# 14-Counter74LS192.net
KiCad netlist of a schematic drawn in Altium Designer
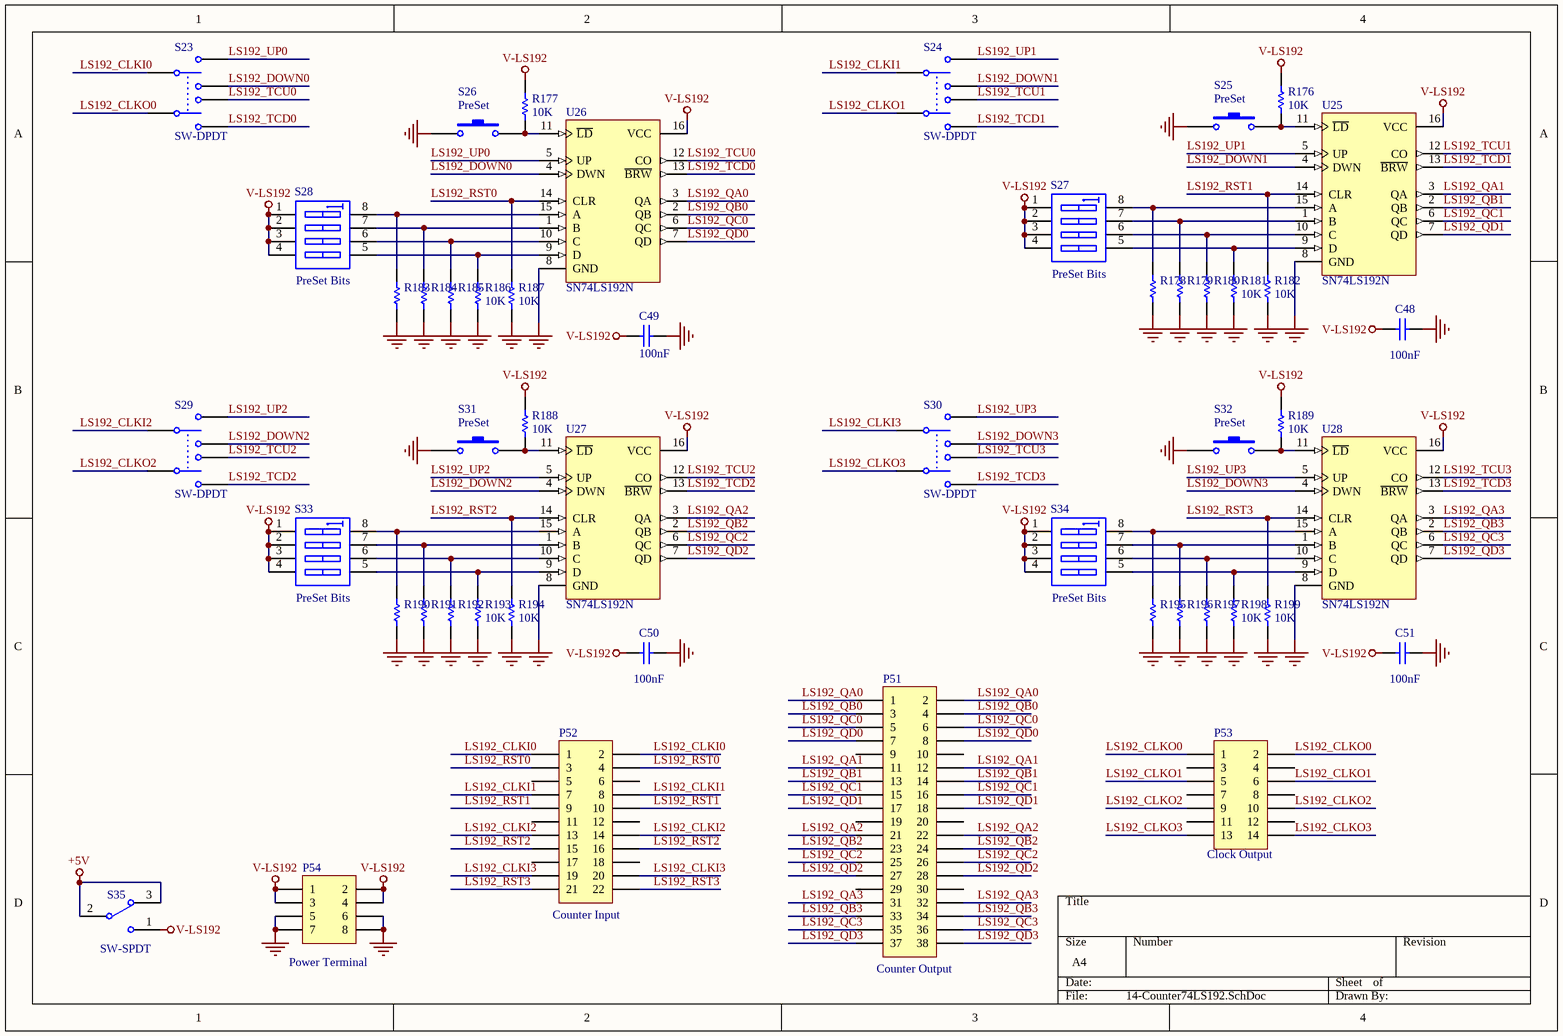
[diagram p0: 14-Counter74LS192.SchDoc]

(export (version "E")
  (design (tool "Eeschema 10.0.6"))
  (components
    (comp (ref "C48")
      (value "100nF")
      (footprint "c-0805")
      (description "Capacitor")
      (fields (field (name "Comment") "104") (field (name "PUBLISHER") "Altium Limited"))
      (libsource (lib "Miscellaneous Devices") (part "Cap"))
    )
    (comp (ref "C49")
      (value "100nF")
      (footprint "c-0805")
      (description "Capacitor")
      (fields (field (name "Comment") "104") (field (name "PUBLISHER") "Altium Limited"))
      (libsource (lib "Miscellaneous Devices") (part "Cap"))
    )
    (comp (ref "C50")
      (value "100nF")
      (footprint "c-0805")
      (description "Capacitor")
      (fields (field (name "Comment") "104") (field (name "PUBLISHER") "Altium Limited"))
      (libsource (lib "Miscellaneous Devices") (part "Cap"))
    )
    (comp (ref "C51")
      (value "100nF")
      (footprint "c-0805")
      (description "Capacitor")
      (fields (field (name "Comment") "104") (field (name "PUBLISHER") "Altium Limited"))
      (libsource (lib "Miscellaneous Devices") (part "Cap"))
    )
    (comp (ref "P51")
      (value "Counter Output")
      (footprint "HDR2X19")
      (description "Header, 19-Pin, Dual row")
      (fields (field (name "Comment") "Header 19X2"))
      (libsource (lib "Miscellaneous Connectors") (part "Header 19X2"))
    )
    (comp (ref "P52")
      (value "Counter Input")
      (footprint "HDR2X11")
      (description "Header, 11-Pin, Dual row")
      (fields (field (name "Comment") "Header 11X2"))
      (libsource (lib "Miscellaneous Connectors") (part "Header 11X2"))
    )
    (comp (ref "P53")
      (value "Clock Output")
      (footprint "HDR2X7")
      (description "Header, 7-Pin, Dual row")
      (fields (field (name "Comment") "Header 7X2"))
      (libsource (lib "Miscellaneous Connectors") (part "Header 7X2"))
    )
    (comp (ref "P54")
      (value "Header 4X2")
      (footprint "HDR2X4")
      (description "Header, 4-Pin, Dual row")
      (fields (field (name "PUBLISHER") "Power Terminal"))
      (libsource (lib "Miscellaneous Connectors") (part "Header 4X2"))
    )
    (comp (ref "R176")
      (value "10K")
      (footprint "r-0805")
      (description "Resistor")
      (fields (field (name "PUBLISHER") "Altium Limited"))
      (libsource (lib "Miscellaneous Devices") (part "Res1"))
    )
    (comp (ref "R177")
      (value "10K")
      (footprint "r-0805")
      (description "Resistor")
      (fields (field (name "PUBLISHER") "Altium Limited"))
      (libsource (lib "Miscellaneous Devices") (part "Res1"))
    )
    (comp (ref "R178")
      (value "103")
      (footprint "r-0805")
      (description "Resistor")
      (fields (field (name "PUBLISHER") "Altium Limited"))
      (libsource (lib "Miscellaneous Devices") (part "Res1"))
    )
    (comp (ref "R179")
      (value "103")
      (footprint "r-0805")
      (description "Resistor")
      (fields (field (name "PUBLISHER") "Altium Limited"))
      (libsource (lib "Miscellaneous Devices") (part "Res1"))
    )
    (comp (ref "R180")
      (value "103")
      (footprint "r-0805")
      (description "Resistor")
      (fields (field (name "PUBLISHER") "Altium Limited"))
      (libsource (lib "Miscellaneous Devices") (part "Res1"))
    )
    (comp (ref "R181")
      (value "10K")
      (footprint "r-0805")
      (description "Resistor")
      (fields (field (name "PUBLISHER") "Altium Limited"))
      (libsource (lib "Miscellaneous Devices") (part "Res1"))
    )
    (comp (ref "R182")
      (value "10K")
      (footprint "r-0805")
      (description "Resistor")
      (fields (field (name "PUBLISHER") "Altium Limited"))
      (libsource (lib "Miscellaneous Devices") (part "Res1"))
    )
    (comp (ref "R183")
      (value "103")
      (footprint "r-0805")
      (description "Resistor")
      (fields (field (name "PUBLISHER") "Altium Limited"))
      (libsource (lib "Miscellaneous Devices") (part "Res1"))
    )
    (comp (ref "R184")
      (value "103")
      (footprint "r-0805")
      (description "Resistor")
      (fields (field (name "PUBLISHER") "Altium Limited"))
      (libsource (lib "Miscellaneous Devices") (part "Res1"))
    )
    (comp (ref "R185")
      (value "103")
      (footprint "r-0805")
      (description "Resistor")
      (fields (field (name "PUBLISHER") "Altium Limited"))
      (libsource (lib "Miscellaneous Devices") (part "Res1"))
    )
    (comp (ref "R186")
      (value "10K")
      (footprint "r-0805")
      (description "Resistor")
      (fields (field (name "PUBLISHER") "Altium Limited"))
      (libsource (lib "Miscellaneous Devices") (part "Res1"))
    )
    (comp (ref "R187")
      (value "10K")
      (footprint "r-0805")
      (description "Resistor")
      (fields (field (name "PUBLISHER") "Altium Limited"))
      (libsource (lib "Miscellaneous Devices") (part "Res1"))
    )
    (comp (ref "R188")
      (value "10K")
      (footprint "r-0805")
      (description "Resistor")
      (fields (field (name "PUBLISHER") "Altium Limited"))
      (libsource (lib "Miscellaneous Devices") (part "Res1"))
    )
    (comp (ref "R189")
      (value "10K")
      (footprint "r-0805")
      (description "Resistor")
      (fields (field (name "PUBLISHER") "Altium Limited"))
      (libsource (lib "Miscellaneous Devices") (part "Res1"))
    )
    (comp (ref "R190")
      (value "103")
      (footprint "r-0805")
      (description "Resistor")
      (fields (field (name "PUBLISHER") "Altium Limited"))
      (libsource (lib "Miscellaneous Devices") (part "Res1"))
    )
    (comp (ref "R191")
      (value "103")
      (footprint "r-0805")
      (description "Resistor")
      (fields (field (name "PUBLISHER") "Altium Limited"))
      (libsource (lib "Miscellaneous Devices") (part "Res1"))
    )
    (comp (ref "R192")
      (value "103")
      (footprint "r-0805")
      (description "Resistor")
      (fields (field (name "PUBLISHER") "Altium Limited"))
      (libsource (lib "Miscellaneous Devices") (part "Res1"))
    )
    (comp (ref "R193")
      (value "10K")
      (footprint "r-0805")
      (description "Resistor")
      (fields (field (name "PUBLISHER") "Altium Limited"))
      (libsource (lib "Miscellaneous Devices") (part "Res1"))
    )
    (comp (ref "R194")
      (value "10K")
      (footprint "r-0805")
      (description "Resistor")
      (fields (field (name "PUBLISHER") "Altium Limited"))
      (libsource (lib "Miscellaneous Devices") (part "Res1"))
    )
    (comp (ref "R195")
      (value "103")
      (footprint "r-0805")
      (description "Resistor")
      (fields (field (name "PUBLISHER") "Altium Limited"))
      (libsource (lib "Miscellaneous Devices") (part "Res1"))
    )
    (comp (ref "R196")
      (value "103")
      (footprint "r-0805")
      (description "Resistor")
      (fields (field (name "PUBLISHER") "Altium Limited"))
      (libsource (lib "Miscellaneous Devices") (part "Res1"))
    )
    (comp (ref "R197")
      (value "103")
      (footprint "r-0805")
      (description "Resistor")
      (fields (field (name "PUBLISHER") "Altium Limited"))
      (libsource (lib "Miscellaneous Devices") (part "Res1"))
    )
    (comp (ref "R198")
      (value "10K")
      (footprint "r-0805")
      (description "Resistor")
      (fields (field (name "PUBLISHER") "Altium Limited"))
      (libsource (lib "Miscellaneous Devices") (part "Res1"))
    )
    (comp (ref "R199")
      (value "10K")
      (footprint "r-0805")
      (description "Resistor")
      (fields (field (name "PUBLISHER") "Altium Limited"))
      (libsource (lib "Miscellaneous Devices") (part "Res1"))
    )
    (comp (ref "S23")
      (value "SW-DPDT")
      (footprint "DPDT-6")
      (description "Double-Pole, Double-Throw Switch")
      (fields (field (name "PUBLISHER") "Altium Limited"))
      (libsource (lib "Miscellaneous Devices") (part "SW-DPDT"))
    )
    (comp (ref "S24")
      (value "SW-DPDT")
      (footprint "DPDT-6")
      (description "Double-Pole, Double-Throw Switch")
      (fields (field (name "PUBLISHER") "Altium Limited"))
      (libsource (lib "Miscellaneous Devices") (part "SW-DPDT"))
    )
    (comp (ref "S25")
      (value "PreSet")
      (footprint "SW2")
      (description "Switch")
      (fields (field (name "Comment") "SW-PB"))
      (libsource (lib "Miscellaneous Devices") (part "SW-PB"))
    )
    (comp (ref "S26")
      (value "PreSet")
      (footprint "SW2")
      (description "Switch")
      (fields (field (name "Comment") "SW-PB"))
      (libsource (lib "Miscellaneous Devices") (part "SW-PB"))
    )
    (comp (ref "S27")
      (value "PreSet Bits")
      (footprint "SW-DIP4")
      (description "DIP Switch, 4 Position, SPST")
      (fields (field (name "Comment") "SW DIP-4"))
      (libsource (lib "Miscellaneous Devices") (part "SW DIP-4"))
    )
    (comp (ref "S28")
      (value "PreSet Bits")
      (footprint "SW-DIP4")
      (description "DIP Switch, 4 Position, SPST")
      (fields (field (name "Comment") "SW DIP-4"))
      (libsource (lib "Miscellaneous Devices") (part "SW DIP-4"))
    )
    (comp (ref "S29")
      (value "SW-DPDT")
      (footprint "DPDT-6")
      (description "Double-Pole, Double-Throw Switch")
      (fields (field (name "PUBLISHER") "Altium Limited"))
      (libsource (lib "Miscellaneous Devices") (part "SW-DPDT"))
    )
    (comp (ref "S30")
      (value "SW-DPDT")
      (footprint "DPDT-6")
      (description "Double-Pole, Double-Throw Switch")
      (fields (field (name "PUBLISHER") "Altium Limited"))
      (libsource (lib "Miscellaneous Devices") (part "SW-DPDT"))
    )
    (comp (ref "S31")
      (value "PreSet")
      (footprint "SW2")
      (description "Switch")
      (fields (field (name "Comment") "SW-PB"))
      (libsource (lib "Miscellaneous Devices") (part "SW-PB"))
    )
    (comp (ref "S32")
      (value "PreSet")
      (footprint "SW2")
      (description "Switch")
      (fields (field (name "Comment") "SW-PB"))
      (libsource (lib "Miscellaneous Devices") (part "SW-PB"))
    )
    (comp (ref "S33")
      (value "PreSet Bits")
      (footprint "SW-DIP4")
      (description "DIP Switch, 4 Position, SPST")
      (fields (field (name "Comment") "SW DIP-4"))
      (libsource (lib "Miscellaneous Devices") (part "SW DIP-4"))
    )
    (comp (ref "S34")
      (value "PreSet Bits")
      (footprint "SW-DIP4")
      (description "DIP Switch, 4 Position, SPST")
      (fields (field (name "Comment") "SW DIP-4"))
      (libsource (lib "Miscellaneous Devices") (part "SW DIP-4"))
    )
    (comp (ref "S35")
      (value "SW-SPDT")
      (footprint "SW-DIP1SMD")
      (description "SPDT Subminiature Toggle Switch, Right Angle Mounting, Vertical Actuation")
      (fields (field (name "PUBLISHER") "Altium Limited"))
      (libsource (lib "Miscellaneous Devices") (part "SW-SPDT"))
    )
    (comp (ref "U25")
      (value "SN74LS192N")
      (footprint "DIP16")
      (description "Synchronous 4-Bit Up/Down Counter (Dual Clock with Clear)")
      (fields (field (name "PUBLISHER") "Altium Limited"))
      (libsource (lib "TI Logic Counter") (part "SN74LS192N"))
    )
    (comp (ref "U26")
      (value "SN74LS192N")
      (footprint "DIP16")
      (description "Synchronous 4-Bit Up/Down Counter (Dual Clock with Clear)")
      (fields (field (name "PUBLISHER") "Altium Limited"))
      (libsource (lib "TI Logic Counter") (part "SN74LS192N"))
    )
    (comp (ref "U27")
      (value "SN74LS192N")
      (footprint "DIP16")
      (description "Synchronous 4-Bit Up/Down Counter (Dual Clock with Clear)")
      (fields (field (name "PUBLISHER") "Altium Limited"))
      (libsource (lib "TI Logic Counter") (part "SN74LS192N"))
    )
    (comp (ref "U28")
      (value "SN74LS192N")
      (footprint "DIP16")
      (description "Synchronous 4-Bit Up/Down Counter (Dual Clock with Clear)")
      (fields (field (name "PUBLISHER") "Altium Limited"))
      (libsource (lib "TI Logic Counter") (part "SN74LS192N"))
    )
  )
  (nets
    (net (code "1") (name "+5V") (class "Default")
      (node (ref "S35") (pin "2") (pinfunction "2_2") (pintype "passive"))
      (node (ref "S35") (pin "3") (pinfunction "3_3") (pintype "passive"))
    )
    (net (code "2") (name "/LS192_CLKI0") (class "Default")
      (node (ref "P52") (pin "1") (pinfunction "1_1") (pintype "passive"))
      (node (ref "P52") (pin "2") (pinfunction "2_2") (pintype "passive"))
      (node (ref "S23") (pin "1") (pinfunction "1_1") (pintype "passive"))
    )
    (net (code "3") (name "/LS192_CLKI1") (class "Default")
      (node (ref "P52") (pin "7") (pinfunction "7_7") (pintype "passive"))
      (node (ref "P52") (pin "8") (pinfunction "8_8") (pintype "passive"))
      (node (ref "S24") (pin "1") (pinfunction "1_1") (pintype "passive"))
    )
    (net (code "4") (name "/LS192_CLKI2") (class "Default")
      (node (ref "P52") (pin "13") (pinfunction "13_13") (pintype "passive"))
      (node (ref "P52") (pin "14") (pinfunction "14_14") (pintype "passive"))
      (node (ref "S29") (pin "1") (pinfunction "1_1") (pintype "passive"))
    )
    (net (code "5") (name "/LS192_CLKI3") (class "Default")
      (node (ref "P52") (pin "19") (pinfunction "19_19") (pintype "passive"))
      (node (ref "P52") (pin "20") (pinfunction "20_20") (pintype "passive"))
      (node (ref "S30") (pin "1") (pinfunction "1_1") (pintype "passive"))
    )
    (net (code "6") (name "/LS192_CLKO0") (class "Default")
      (node (ref "P53") (pin "1") (pinfunction "1_1") (pintype "passive"))
      (node (ref "P53") (pin "2") (pinfunction "2_2") (pintype "passive"))
      (node (ref "S23") (pin "4") (pinfunction "4_4") (pintype "passive"))
    )
    (net (code "7") (name "/LS192_CLKO1") (class "Default")
      (node (ref "P53") (pin "5") (pinfunction "5_5") (pintype "passive"))
      (node (ref "P53") (pin "6") (pinfunction "6_6") (pintype "passive"))
      (node (ref "S24") (pin "4") (pinfunction "4_4") (pintype "passive"))
    )
    (net (code "8") (name "/LS192_CLKO2") (class "Default")
      (node (ref "P53") (pin "10") (pinfunction "10_10") (pintype "passive"))
      (node (ref "P53") (pin "9") (pinfunction "9_9") (pintype "passive"))
      (node (ref "S29") (pin "4") (pinfunction "4_4") (pintype "passive"))
    )
    (net (code "9") (name "/LS192_CLKO3") (class "Default")
      (node (ref "P53") (pin "13") (pinfunction "13_13") (pintype "passive"))
      (node (ref "P53") (pin "14") (pinfunction "14_14") (pintype "passive"))
      (node (ref "S30") (pin "4") (pinfunction "4_4") (pintype "passive"))
    )
    (net (code "10") (name "/LS192_DOWN0") (class "Default")
      (node (ref "S23") (pin "3") (pinfunction "3_3") (pintype "passive"))
      (node (ref "U26") (pin "4") (pinfunction "DWN_4") (pintype "input"))
    )
    (net (code "11") (name "/LS192_DOWN1") (class "Default")
      (node (ref "S24") (pin "3") (pinfunction "3_3") (pintype "passive"))
      (node (ref "U25") (pin "4") (pinfunction "DWN_4") (pintype "input"))
    )
    (net (code "12") (name "/LS192_DOWN2") (class "Default")
      (node (ref "S29") (pin "3") (pinfunction "3_3") (pintype "passive"))
      (node (ref "U27") (pin "4") (pinfunction "DWN_4") (pintype "input"))
    )
    (net (code "13") (name "/LS192_DOWN3") (class "Default")
      (node (ref "S30") (pin "3") (pinfunction "3_3") (pintype "passive"))
      (node (ref "U28") (pin "4") (pinfunction "DWN_4") (pintype "input"))
    )
    (net (code "14") (name "/LS192_QA0") (class "Default")
      (node (ref "P51") (pin "1") (pinfunction "1_1") (pintype "passive"))
      (node (ref "P51") (pin "2") (pinfunction "2_2") (pintype "passive"))
      (node (ref "U26") (pin "3") (pinfunction "QA_3") (pintype "output"))
    )
    (net (code "15") (name "/LS192_QA1") (class "Default")
      (node (ref "P51") (pin "11") (pinfunction "11_11") (pintype "passive"))
      (node (ref "P51") (pin "12") (pinfunction "12_12") (pintype "passive"))
      (node (ref "U25") (pin "3") (pinfunction "QA_3") (pintype "output"))
    )
    (net (code "16") (name "/LS192_QA2") (class "Default")
      (node (ref "P51") (pin "21") (pinfunction "21_21") (pintype "passive"))
      (node (ref "P51") (pin "22") (pinfunction "22_22") (pintype "passive"))
      (node (ref "U27") (pin "3") (pinfunction "QA_3") (pintype "output"))
    )
    (net (code "17") (name "/LS192_QA3") (class "Default")
      (node (ref "P51") (pin "31") (pinfunction "31_31") (pintype "passive"))
      (node (ref "P51") (pin "32") (pinfunction "32_32") (pintype "passive"))
      (node (ref "U28") (pin "3") (pinfunction "QA_3") (pintype "output"))
    )
    (net (code "18") (name "/LS192_QB0") (class "Default")
      (node (ref "P51") (pin "3") (pinfunction "3_3") (pintype "passive"))
      (node (ref "P51") (pin "4") (pinfunction "4_4") (pintype "passive"))
      (node (ref "U26") (pin "2") (pinfunction "QB_2") (pintype "output"))
    )
    (net (code "19") (name "/LS192_QB1") (class "Default")
      (node (ref "P51") (pin "13") (pinfunction "13_13") (pintype "passive"))
      (node (ref "P51") (pin "14") (pinfunction "14_14") (pintype "passive"))
      (node (ref "U25") (pin "2") (pinfunction "QB_2") (pintype "output"))
    )
    (net (code "20") (name "/LS192_QB2") (class "Default")
      (node (ref "P51") (pin "23") (pinfunction "23_23") (pintype "passive"))
      (node (ref "P51") (pin "24") (pinfunction "24_24") (pintype "passive"))
      (node (ref "U27") (pin "2") (pinfunction "QB_2") (pintype "output"))
    )
    (net (code "21") (name "/LS192_QB3") (class "Default")
      (node (ref "P51") (pin "33") (pinfunction "33_33") (pintype "passive"))
      (node (ref "P51") (pin "34") (pinfunction "34_34") (pintype "passive"))
      (node (ref "U28") (pin "2") (pinfunction "QB_2") (pintype "output"))
    )
    (net (code "22") (name "/LS192_QC0") (class "Default")
      (node (ref "P51") (pin "5") (pinfunction "5_5") (pintype "passive"))
      (node (ref "P51") (pin "6") (pinfunction "6_6") (pintype "passive"))
      (node (ref "U26") (pin "6") (pinfunction "QC_6") (pintype "output"))
    )
    (net (code "23") (name "/LS192_QC1") (class "Default")
      (node (ref "P51") (pin "15") (pinfunction "15_15") (pintype "passive"))
      (node (ref "P51") (pin "16") (pinfunction "16_16") (pintype "passive"))
      (node (ref "U25") (pin "6") (pinfunction "QC_6") (pintype "output"))
    )
    (net (code "24") (name "/LS192_QC2") (class "Default")
      (node (ref "P51") (pin "25") (pinfunction "25_25") (pintype "passive"))
      (node (ref "P51") (pin "26") (pinfunction "26_26") (pintype "passive"))
      (node (ref "U27") (pin "6") (pinfunction "QC_6") (pintype "output"))
    )
    (net (code "25") (name "/LS192_QC3") (class "Default")
      (node (ref "P51") (pin "35") (pinfunction "35_35") (pintype "passive"))
      (node (ref "P51") (pin "36") (pinfunction "36_36") (pintype "passive"))
      (node (ref "U28") (pin "6") (pinfunction "QC_6") (pintype "output"))
    )
    (net (code "26") (name "/LS192_QD0") (class "Default")
      (node (ref "P51") (pin "7") (pinfunction "7_7") (pintype "passive"))
      (node (ref "P51") (pin "8") (pinfunction "8_8") (pintype "passive"))
      (node (ref "U26") (pin "7") (pinfunction "QD_7") (pintype "output"))
    )
    (net (code "27") (name "/LS192_QD1") (class "Default")
      (node (ref "P51") (pin "17") (pinfunction "17_17") (pintype "passive"))
      (node (ref "P51") (pin "18") (pinfunction "18_18") (pintype "passive"))
      (node (ref "U25") (pin "7") (pinfunction "QD_7") (pintype "output"))
    )
    (net (code "28") (name "/LS192_QD2") (class "Default")
      (node (ref "P51") (pin "27") (pinfunction "27_27") (pintype "passive"))
      (node (ref "P51") (pin "28") (pinfunction "28_28") (pintype "passive"))
      (node (ref "U27") (pin "7") (pinfunction "QD_7") (pintype "output"))
    )
    (net (code "29") (name "/LS192_QD3") (class "Default")
      (node (ref "P51") (pin "37") (pinfunction "37_37") (pintype "passive"))
      (node (ref "P51") (pin "38") (pinfunction "38_38") (pintype "passive"))
      (node (ref "U28") (pin "7") (pinfunction "QD_7") (pintype "output"))
    )
    (net (code "30") (name "/LS192_RST0") (class "Default")
      (node (ref "P52") (pin "3") (pinfunction "3_3") (pintype "passive"))
      (node (ref "P52") (pin "4") (pinfunction "4_4") (pintype "passive"))
      (node (ref "R187") (pin "2") (pinfunction "2_2") (pintype "passive"))
      (node (ref "U26") (pin "14") (pinfunction "CLR_14") (pintype "input"))
    )
    (net (code "31") (name "/LS192_RST1") (class "Default")
      (node (ref "P52") (pin "10") (pinfunction "10_10") (pintype "passive"))
      (node (ref "P52") (pin "9") (pinfunction "9_9") (pintype "passive"))
      (node (ref "R182") (pin "2") (pinfunction "2_2") (pintype "passive"))
      (node (ref "U25") (pin "14") (pinfunction "CLR_14") (pintype "input"))
    )
    (net (code "32") (name "/LS192_RST2") (class "Default")
      (node (ref "P52") (pin "15") (pinfunction "15_15") (pintype "passive"))
      (node (ref "P52") (pin "16") (pinfunction "16_16") (pintype "passive"))
      (node (ref "R194") (pin "2") (pinfunction "2_2") (pintype "passive"))
      (node (ref "U27") (pin "14") (pinfunction "CLR_14") (pintype "input"))
    )
    (net (code "33") (name "/LS192_RST3") (class "Default")
      (node (ref "P52") (pin "21") (pinfunction "21_21") (pintype "passive"))
      (node (ref "P52") (pin "22") (pinfunction "22_22") (pintype "passive"))
      (node (ref "R199") (pin "2") (pinfunction "2_2") (pintype "passive"))
      (node (ref "U28") (pin "14") (pinfunction "CLR_14") (pintype "input"))
    )
    (net (code "34") (name "/LS192_TCD0") (class "Default")
      (node (ref "S23") (pin "6") (pinfunction "6_6") (pintype "passive"))
      (node (ref "U26") (pin "13") (pinfunction "~{BRW}_13") (pintype "output"))
    )
    (net (code "35") (name "/LS192_TCD1") (class "Default")
      (node (ref "S24") (pin "6") (pinfunction "6_6") (pintype "passive"))
      (node (ref "U25") (pin "13") (pinfunction "~{BRW}_13") (pintype "output"))
    )
    (net (code "36") (name "/LS192_TCD2") (class "Default")
      (node (ref "S29") (pin "6") (pinfunction "6_6") (pintype "passive"))
      (node (ref "U27") (pin "13") (pinfunction "~{BRW}_13") (pintype "output"))
    )
    (net (code "37") (name "/LS192_TCD3") (class "Default")
      (node (ref "S30") (pin "6") (pinfunction "6_6") (pintype "passive"))
      (node (ref "U28") (pin "13") (pinfunction "~{BRW}_13") (pintype "output"))
    )
    (net (code "38") (name "/LS192_TCU0") (class "Default")
      (node (ref "S23") (pin "5") (pinfunction "5_5") (pintype "passive"))
      (node (ref "U26") (pin "12") (pinfunction "CO_12") (pintype "output"))
    )
    (net (code "39") (name "/LS192_TCU1") (class "Default")
      (node (ref "S24") (pin "5") (pinfunction "5_5") (pintype "passive"))
      (node (ref "U25") (pin "12") (pinfunction "CO_12") (pintype "output"))
    )
    (net (code "40") (name "/LS192_TCU2") (class "Default")
      (node (ref "S29") (pin "5") (pinfunction "5_5") (pintype "passive"))
      (node (ref "U27") (pin "12") (pinfunction "CO_12") (pintype "output"))
    )
    (net (code "41") (name "/LS192_TCU3") (class "Default")
      (node (ref "S30") (pin "5") (pinfunction "5_5") (pintype "passive"))
      (node (ref "U28") (pin "12") (pinfunction "CO_12") (pintype "output"))
    )
    (net (code "42") (name "/LS192_UP0") (class "Default")
      (node (ref "S23") (pin "2") (pinfunction "2_2") (pintype "passive"))
      (node (ref "U26") (pin "5") (pinfunction "UP_5") (pintype "input"))
    )
    (net (code "43") (name "/LS192_UP1") (class "Default")
      (node (ref "S24") (pin "2") (pinfunction "2_2") (pintype "passive"))
      (node (ref "U25") (pin "5") (pinfunction "UP_5") (pintype "input"))
    )
    (net (code "44") (name "/LS192_UP2") (class "Default")
      (node (ref "S29") (pin "2") (pinfunction "2_2") (pintype "passive"))
      (node (ref "U27") (pin "5") (pinfunction "UP_5") (pintype "input"))
    )
    (net (code "45") (name "/LS192_UP3") (class "Default")
      (node (ref "S30") (pin "2") (pinfunction "2_2") (pintype "passive"))
      (node (ref "U28") (pin "5") (pinfunction "UP_5") (pintype "input"))
    )
    (net (code "46") (name "GND") (class "Default")
      (node (ref "C48") (pin "2") (pinfunction "2_2") (pintype "passive"))
      (node (ref "C49") (pin "2") (pinfunction "2_2") (pintype "passive"))
      (node (ref "C50") (pin "2") (pinfunction "2_2") (pintype "passive"))
      (node (ref "C51") (pin "2") (pinfunction "2_2") (pintype "passive"))
      (node (ref "P54") (pin "5") (pinfunction "5_5") (pintype "passive"))
      (node (ref "P54") (pin "6") (pinfunction "6_6") (pintype "passive"))
      (node (ref "P54") (pin "7") (pinfunction "7_7") (pintype "passive"))
      (node (ref "P54") (pin "8") (pinfunction "8_8") (pintype "passive"))
      (node (ref "R178") (pin "1") (pinfunction "1_1") (pintype "passive"))
      (node (ref "R179") (pin "1") (pinfunction "1_1") (pintype "passive"))
      (node (ref "R180") (pin "1") (pinfunction "1_1") (pintype "passive"))
      (node (ref "R181") (pin "1") (pinfunction "1_1") (pintype "passive"))
      (node (ref "R182") (pin "1") (pinfunction "1_1") (pintype "passive"))
      (node (ref "R183") (pin "1") (pinfunction "1_1") (pintype "passive"))
      (node (ref "R184") (pin "1") (pinfunction "1_1") (pintype "passive"))
      (node (ref "R185") (pin "1") (pinfunction "1_1") (pintype "passive"))
      (node (ref "R186") (pin "1") (pinfunction "1_1") (pintype "passive"))
      (node (ref "R187") (pin "1") (pinfunction "1_1") (pintype "passive"))
      (node (ref "R190") (pin "1") (pinfunction "1_1") (pintype "passive"))
      (node (ref "R191") (pin "1") (pinfunction "1_1") (pintype "passive"))
      (node (ref "R192") (pin "1") (pinfunction "1_1") (pintype "passive"))
      (node (ref "R193") (pin "1") (pinfunction "1_1") (pintype "passive"))
      (node (ref "R194") (pin "1") (pinfunction "1_1") (pintype "passive"))
      (node (ref "R195") (pin "1") (pinfunction "1_1") (pintype "passive"))
      (node (ref "R196") (pin "1") (pinfunction "1_1") (pintype "passive"))
      (node (ref "R197") (pin "1") (pinfunction "1_1") (pintype "passive"))
      (node (ref "R198") (pin "1") (pinfunction "1_1") (pintype "passive"))
      (node (ref "R199") (pin "1") (pinfunction "1_1") (pintype "passive"))
      (node (ref "S25") (pin "1") (pinfunction "1_1") (pintype "passive"))
      (node (ref "S26") (pin "1") (pinfunction "1_1") (pintype "passive"))
      (node (ref "S31") (pin "1") (pinfunction "1_1") (pintype "passive"))
      (node (ref "S32") (pin "1") (pinfunction "1_1") (pintype "passive"))
      (node (ref "U25") (pin "8") (pinfunction "GND_8") (pintype "power_in"))
      (node (ref "U26") (pin "8") (pinfunction "GND_8") (pintype "power_in"))
      (node (ref "U27") (pin "8") (pinfunction "GND_8") (pintype "power_in"))
      (node (ref "U28") (pin "8") (pinfunction "GND_8") (pintype "power_in"))
    )
    (net (code "47") (name "Net-(S27-B1)") (class "Default")
      (node (ref "R178") (pin "2") (pinfunction "2_2") (pintype "passive"))
      (node (ref "S27") (pin "8") (pinfunction "B1_8") (pintype "passive"))
      (node (ref "U25") (pin "15") (pinfunction "A_15") (pintype "input"))
    )
    (net (code "48") (name "Net-(S27-B2)") (class "Default")
      (node (ref "R179") (pin "2") (pinfunction "2_2") (pintype "passive"))
      (node (ref "S27") (pin "7") (pinfunction "B2_7") (pintype "passive"))
      (node (ref "U25") (pin "1") (pinfunction "B_1") (pintype "input"))
    )
    (net (code "49") (name "Net-(S27-B3)") (class "Default")
      (node (ref "R180") (pin "2") (pinfunction "2_2") (pintype "passive"))
      (node (ref "S27") (pin "6") (pinfunction "B3_6") (pintype "passive"))
      (node (ref "U25") (pin "10") (pinfunction "C_10") (pintype "input"))
    )
    (net (code "50") (name "Net-(S27-B4)") (class "Default")
      (node (ref "R181") (pin "2") (pinfunction "2_2") (pintype "passive"))
      (node (ref "S27") (pin "5") (pinfunction "B4_5") (pintype "passive"))
      (node (ref "U25") (pin "9") (pinfunction "D_9") (pintype "input"))
    )
    (net (code "51") (name "Net-(S28-B1)") (class "Default")
      (node (ref "R183") (pin "2") (pinfunction "2_2") (pintype "passive"))
      (node (ref "S28") (pin "8") (pinfunction "B1_8") (pintype "passive"))
      (node (ref "U26") (pin "15") (pinfunction "A_15") (pintype "input"))
    )
    (net (code "52") (name "Net-(S28-B2)") (class "Default")
      (node (ref "R184") (pin "2") (pinfunction "2_2") (pintype "passive"))
      (node (ref "S28") (pin "7") (pinfunction "B2_7") (pintype "passive"))
      (node (ref "U26") (pin "1") (pinfunction "B_1") (pintype "input"))
    )
    (net (code "53") (name "Net-(S28-B3)") (class "Default")
      (node (ref "R185") (pin "2") (pinfunction "2_2") (pintype "passive"))
      (node (ref "S28") (pin "6") (pinfunction "B3_6") (pintype "passive"))
      (node (ref "U26") (pin "10") (pinfunction "C_10") (pintype "input"))
    )
    (net (code "54") (name "Net-(S28-B4)") (class "Default")
      (node (ref "R186") (pin "2") (pinfunction "2_2") (pintype "passive"))
      (node (ref "S28") (pin "5") (pinfunction "B4_5") (pintype "passive"))
      (node (ref "U26") (pin "9") (pinfunction "D_9") (pintype "input"))
    )
    (net (code "55") (name "Net-(S33-B1)") (class "Default")
      (node (ref "R190") (pin "2") (pinfunction "2_2") (pintype "passive"))
      (node (ref "S33") (pin "8") (pinfunction "B1_8") (pintype "passive"))
      (node (ref "U27") (pin "15") (pinfunction "A_15") (pintype "input"))
    )
    (net (code "56") (name "Net-(S33-B2)") (class "Default")
      (node (ref "R191") (pin "2") (pinfunction "2_2") (pintype "passive"))
      (node (ref "S33") (pin "7") (pinfunction "B2_7") (pintype "passive"))
      (node (ref "U27") (pin "1") (pinfunction "B_1") (pintype "input"))
    )
    (net (code "57") (name "Net-(S33-B3)") (class "Default")
      (node (ref "R192") (pin "2") (pinfunction "2_2") (pintype "passive"))
      (node (ref "S33") (pin "6") (pinfunction "B3_6") (pintype "passive"))
      (node (ref "U27") (pin "10") (pinfunction "C_10") (pintype "input"))
    )
    (net (code "58") (name "Net-(S33-B4)") (class "Default")
      (node (ref "R193") (pin "2") (pinfunction "2_2") (pintype "passive"))
      (node (ref "S33") (pin "5") (pinfunction "B4_5") (pintype "passive"))
      (node (ref "U27") (pin "9") (pinfunction "D_9") (pintype "input"))
    )
    (net (code "59") (name "Net-(S34-B1)") (class "Default")
      (node (ref "R195") (pin "2") (pinfunction "2_2") (pintype "passive"))
      (node (ref "S34") (pin "8") (pinfunction "B1_8") (pintype "passive"))
      (node (ref "U28") (pin "15") (pinfunction "A_15") (pintype "input"))
    )
    (net (code "60") (name "Net-(S34-B2)") (class "Default")
      (node (ref "R196") (pin "2") (pinfunction "2_2") (pintype "passive"))
      (node (ref "S34") (pin "7") (pinfunction "B2_7") (pintype "passive"))
      (node (ref "U28") (pin "1") (pinfunction "B_1") (pintype "input"))
    )
    (net (code "61") (name "Net-(S34-B3)") (class "Default")
      (node (ref "R197") (pin "2") (pinfunction "2_2") (pintype "passive"))
      (node (ref "S34") (pin "6") (pinfunction "B3_6") (pintype "passive"))
      (node (ref "U28") (pin "10") (pinfunction "C_10") (pintype "input"))
    )
    (net (code "62") (name "Net-(S34-B4)") (class "Default")
      (node (ref "R198") (pin "2") (pinfunction "2_2") (pintype "passive"))
      (node (ref "S34") (pin "5") (pinfunction "B4_5") (pintype "passive"))
      (node (ref "U28") (pin "9") (pinfunction "D_9") (pintype "input"))
    )
    (net (code "63") (name "Net-(U25-~{LD})") (class "Default")
      (node (ref "R176") (pin "1") (pinfunction "1_1") (pintype "passive"))
      (node (ref "S25") (pin "2") (pinfunction "2_2") (pintype "passive"))
      (node (ref "U25") (pin "11") (pinfunction "~{LD}_11") (pintype "input"))
    )
    (net (code "64") (name "Net-(U26-~{LD})") (class "Default")
      (node (ref "R177") (pin "1") (pinfunction "1_1") (pintype "passive"))
      (node (ref "S26") (pin "2") (pinfunction "2_2") (pintype "passive"))
      (node (ref "U26") (pin "11") (pinfunction "~{LD}_11") (pintype "input"))
    )
    (net (code "65") (name "Net-(U27-~{LD})") (class "Default")
      (node (ref "R188") (pin "1") (pinfunction "1_1") (pintype "passive"))
      (node (ref "S31") (pin "2") (pinfunction "2_2") (pintype "passive"))
      (node (ref "U27") (pin "11") (pinfunction "~{LD}_11") (pintype "input"))
    )
    (net (code "66") (name "Net-(U28-~{LD})") (class "Default")
      (node (ref "R189") (pin "1") (pinfunction "1_1") (pintype "passive"))
      (node (ref "S32") (pin "2") (pinfunction "2_2") (pintype "passive"))
      (node (ref "U28") (pin "11") (pinfunction "~{LD}_11") (pintype "input"))
    )
    (net (code "67") (name "V-LS192") (class "Default")
      (node (ref "C48") (pin "1") (pinfunction "1_1") (pintype "passive"))
      (node (ref "C49") (pin "1") (pinfunction "1_1") (pintype "passive"))
      (node (ref "C50") (pin "1") (pinfunction "1_1") (pintype "passive"))
      (node (ref "C51") (pin "1") (pinfunction "1_1") (pintype "passive"))
      (node (ref "P54") (pin "1") (pinfunction "1_1") (pintype "passive"))
      (node (ref "P54") (pin "2") (pinfunction "2_2") (pintype "passive"))
      (node (ref "P54") (pin "3") (pinfunction "3_3") (pintype "passive"))
      (node (ref "P54") (pin "4") (pinfunction "4_4") (pintype "passive"))
      (node (ref "R176") (pin "2") (pinfunction "2_2") (pintype "passive"))
      (node (ref "R177") (pin "2") (pinfunction "2_2") (pintype "passive"))
      (node (ref "R188") (pin "2") (pinfunction "2_2") (pintype "passive"))
      (node (ref "R189") (pin "2") (pinfunction "2_2") (pintype "passive"))
      (node (ref "S27") (pin "1") (pinfunction "A1_1") (pintype "passive"))
      (node (ref "S27") (pin "2") (pinfunction "A2_2") (pintype "passive"))
      (node (ref "S27") (pin "3") (pinfunction "A3_3") (pintype "passive"))
      (node (ref "S27") (pin "4") (pinfunction "A4_4") (pintype "passive"))
      (node (ref "S28") (pin "1") (pinfunction "A1_1") (pintype "passive"))
      (node (ref "S28") (pin "2") (pinfunction "A2_2") (pintype "passive"))
      (node (ref "S28") (pin "3") (pinfunction "A3_3") (pintype "passive"))
      (node (ref "S28") (pin "4") (pinfunction "A4_4") (pintype "passive"))
      (node (ref "S33") (pin "1") (pinfunction "A1_1") (pintype "passive"))
      (node (ref "S33") (pin "2") (pinfunction "A2_2") (pintype "passive"))
      (node (ref "S33") (pin "3") (pinfunction "A3_3") (pintype "passive"))
      (node (ref "S33") (pin "4") (pinfunction "A4_4") (pintype "passive"))
      (node (ref "S34") (pin "1") (pinfunction "A1_1") (pintype "passive"))
      (node (ref "S34") (pin "2") (pinfunction "A2_2") (pintype "passive"))
      (node (ref "S34") (pin "3") (pinfunction "A3_3") (pintype "passive"))
      (node (ref "S34") (pin "4") (pinfunction "A4_4") (pintype "passive"))
      (node (ref "S35") (pin "1") (pinfunction "1_1") (pintype "passive"))
      (node (ref "U25") (pin "16") (pinfunction "VCC_16") (pintype "power_in"))
      (node (ref "U26") (pin "16") (pinfunction "VCC_16") (pintype "power_in"))
      (node (ref "U27") (pin "16") (pinfunction "VCC_16") (pintype "power_in"))
      (node (ref "U28") (pin "16") (pinfunction "VCC_16") (pintype "power_in"))
    )
    (net (code "68") (name "unconnected-(P51-Pad9)") (class "Default")
      (node (ref "P51") (pin "9") (pinfunction "9_9") (pintype "passive"))
    )
    (net (code "69") (name "unconnected-(P51-Pad10)") (class "Default")
      (node (ref "P51") (pin "10") (pinfunction "10_10") (pintype "passive"))
    )
    (net (code "70") (name "unconnected-(P51-Pad19)") (class "Default")
      (node (ref "P51") (pin "19") (pinfunction "19_19") (pintype "passive"))
    )
    (net (code "71") (name "unconnected-(P51-Pad20)") (class "Default")
      (node (ref "P51") (pin "20") (pinfunction "20_20") (pintype "passive"))
    )
    (net (code "72") (name "unconnected-(P51-Pad29)") (class "Default")
      (node (ref "P51") (pin "29") (pinfunction "29_29") (pintype "passive"))
    )
    (net (code "73") (name "unconnected-(P51-Pad30)") (class "Default")
      (node (ref "P51") (pin "30") (pinfunction "30_30") (pintype "passive"))
    )
    (net (code "74") (name "unconnected-(P52-Pad5)") (class "Default")
      (node (ref "P52") (pin "5") (pinfunction "5_5") (pintype "passive"))
    )
    (net (code "75") (name "unconnected-(P52-Pad6)") (class "Default")
      (node (ref "P52") (pin "6") (pinfunction "6_6") (pintype "passive"))
    )
    (net (code "76") (name "unconnected-(P52-Pad11)") (class "Default")
      (node (ref "P52") (pin "11") (pinfunction "11_11") (pintype "passive"))
    )
    (net (code "77") (name "unconnected-(P52-Pad12)") (class "Default")
      (node (ref "P52") (pin "12") (pinfunction "12_12") (pintype "passive"))
    )
    (net (code "78") (name "unconnected-(P52-Pad17)") (class "Default")
      (node (ref "P52") (pin "17") (pinfunction "17_17") (pintype "passive"))
    )
    (net (code "79") (name "unconnected-(P52-Pad18)") (class "Default")
      (node (ref "P52") (pin "18") (pinfunction "18_18") (pintype "passive"))
    )
    (net (code "80") (name "unconnected-(P53-Pad3)") (class "Default")
      (node (ref "P53") (pin "3") (pinfunction "3_3") (pintype "passive"))
    )
    (net (code "81") (name "unconnected-(P53-Pad4)") (class "Default")
      (node (ref "P53") (pin "4") (pinfunction "4_4") (pintype "passive"))
    )
    (net (code "82") (name "unconnected-(P53-Pad7)") (class "Default")
      (node (ref "P53") (pin "7") (pinfunction "7_7") (pintype "passive"))
    )
    (net (code "83") (name "unconnected-(P53-Pad8)") (class "Default")
      (node (ref "P53") (pin "8") (pinfunction "8_8") (pintype "passive"))
    )
    (net (code "84") (name "unconnected-(P53-Pad11)") (class "Default")
      (node (ref "P53") (pin "11") (pinfunction "11_11") (pintype "passive"))
    )
    (net (code "85") (name "unconnected-(P53-Pad12)") (class "Default")
      (node (ref "P53") (pin "12") (pinfunction "12_12") (pintype "passive"))
    )
  )
)
